# ProPrj_Flipper_-_TweenWave_2025-09-25.net
KiCad netlist of a schematic drawn in EasyEDA Pro
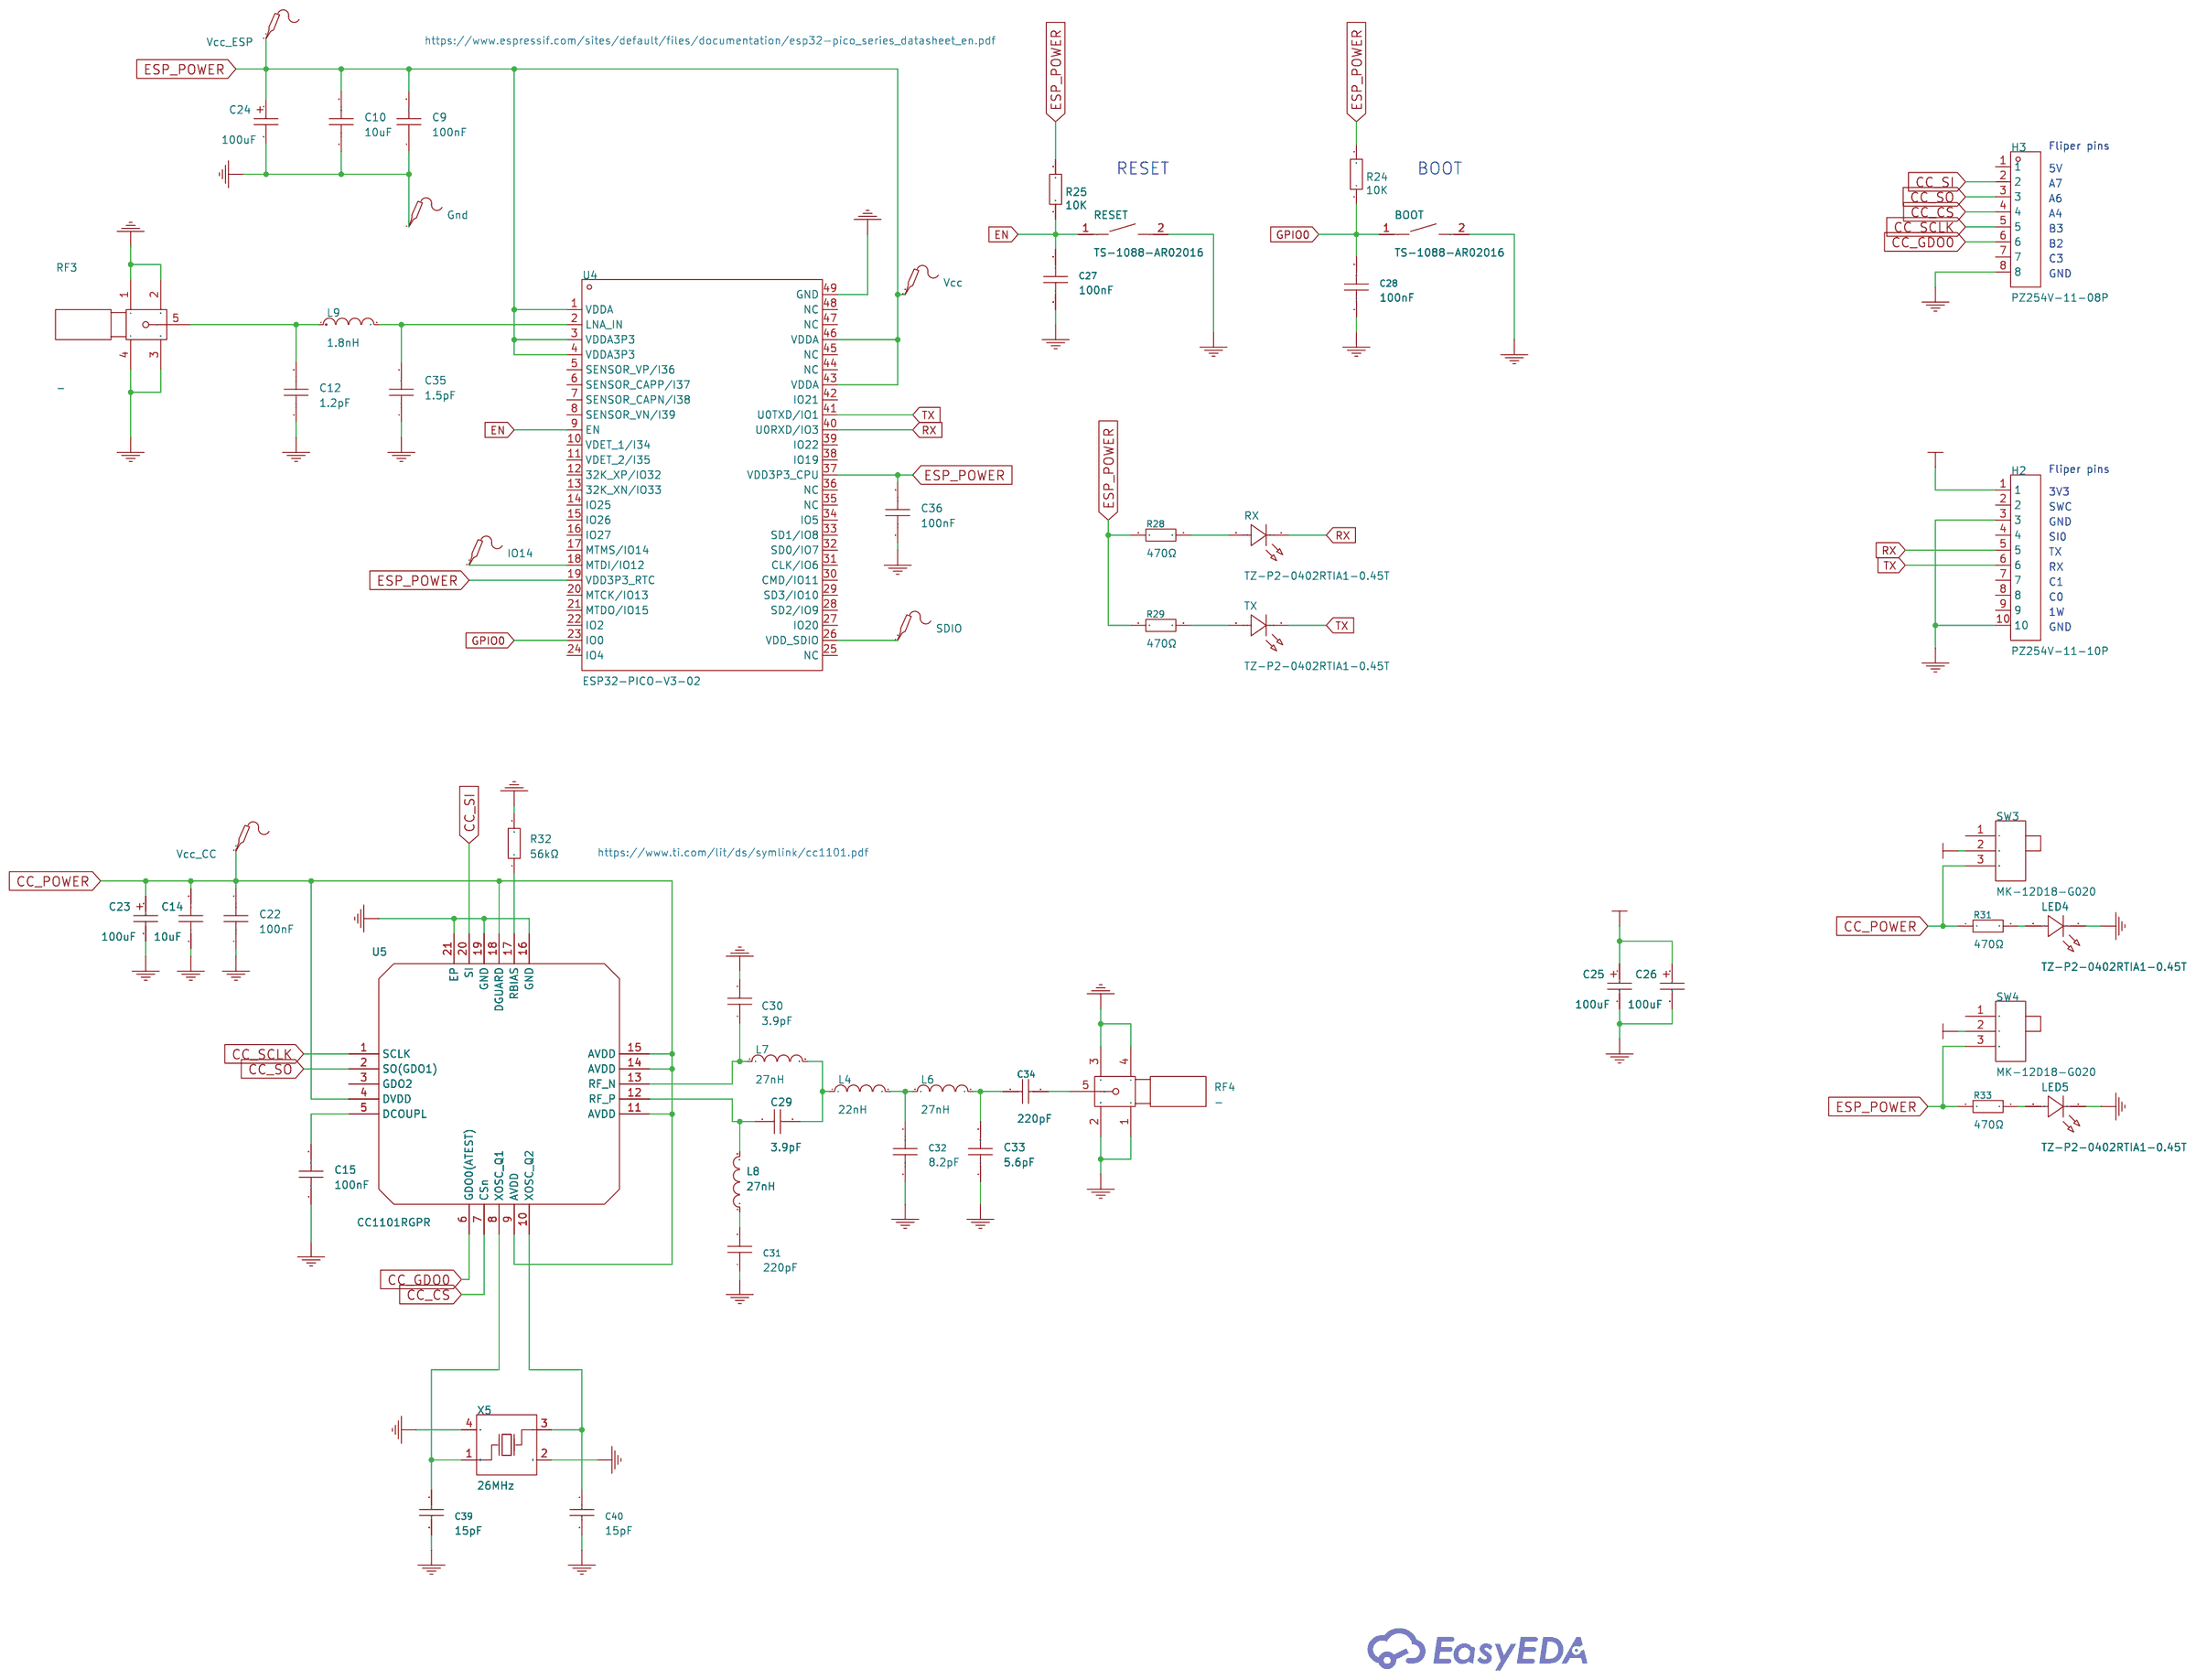
[diagram p0: schematic sheet]

(export (version "E")
  (design (tool "Eeschema 10.0.6"))
  (components
    (comp (ref "BOOT")
      (value "TS-1088-AR02016")
      (footprint "easyedapro:SW-SMD_L3.9-W3.0-P4.45")
      (fields (field (name "Manufacturer") "XUNPU(讯普)"))
      (libsource (lib "easyedapro") (part "TS-1088-AR02016"))
    )
    (comp (ref "C9")
      (value "100nF")
      (footprint "easyedapro:C0603")
      (description "Capacitance:100nF Tolerance:±10% Tolerance:±10% Voltage Rating:50V Temperature Coefficient:X7R")
      (fields
        (field (name "Manufacturer Part") "CC0603KRX7R9BB104")
        (field (name "Manufacturer") "YAGEO(国巨)")
      )
      (libsource (lib "easyedapro") (part "CC0603KRX7R9BB104"))
    )
    (comp (ref "C10")
      (value "10uF")
      (footprint "easyedapro:C0603")
      (fields
        (field (name "Manufacturer Part") "CL10A106MP8NNNC")
        (field (name "Manufacturer") "SAMSUNG(三星)")
      )
      (libsource (lib "easyedapro") (part "CL10A106MP8NNNC"))
    )
    (comp (ref "C12")
      (value "1.2pF")
      (footprint "easyedapro:C0201")
      (fields
        (field (name "Manufacturer Part") "GRM0335C1H1R2BA01D")
        (field (name "Manufacturer") "muRata(村田)")
      )
      (libsource (lib "easyedapro") (part "GRM0335C1H1R2BA01D"))
    )
    (comp (ref "C14")
      (value "10uF")
      (footprint "easyedapro:C0603")
      (fields
        (field (name "Manufacturer Part") "CL10A106MP8NNNC")
        (field (name "Manufacturer") "SAMSUNG(三星)")
      )
      (libsource (lib "easyedapro") (part "CL10A106MP8NNNC"))
    )
    (comp (ref "C15")
      (value "100nF")
      (footprint "easyedapro:C0603")
      (description "Capacitance:100nF Tolerance:±10% Tolerance:±10% Voltage Rating:50V Temperature Coefficient:X7R")
      (fields
        (field (name "Manufacturer Part") "CC0603KRX7R9BB104")
        (field (name "Manufacturer") "YAGEO(国巨)")
      )
      (libsource (lib "easyedapro") (part "CC0603KRX7R9BB104"))
    )
    (comp (ref "C22")
      (value "100nF")
      (footprint "easyedapro:C0603")
      (description "Capacitance:100nF Tolerance:±10% Tolerance:±10% Voltage Rating:50V Temperature Coefficient:X7R")
      (fields
        (field (name "Manufacturer Part") "CC0603KRX7R9BB104")
        (field (name "Manufacturer") "YAGEO(国巨)")
      )
      (libsource (lib "easyedapro") (part "CC0603KRX7R9BB104"))
    )
    (comp (ref "C23")
      (value "100uF")
      (footprint "easyedapro:CASE-B_3528")
      (fields (field (name "Manufacturer Part") "TAJB107K006RNJ") (field (name "Manufacturer") "Kyocera AVX"))
      (libsource (lib "easyedapro") (part "TAJB107K006RNJ"))
    )
    (comp (ref "C24")
      (value "100uF")
      (footprint "easyedapro:CASE-B_3528")
      (fields (field (name "Manufacturer Part") "TAJB107K006RNJ") (field (name "Manufacturer") "Kyocera AVX"))
      (libsource (lib "easyedapro") (part "TAJB107K006RNJ"))
    )
    (comp (ref "C25")
      (value "100uF")
      (footprint "easyedapro:CASE-B_3528")
      (fields (field (name "Manufacturer Part") "TAJB107K006RNJ") (field (name "Manufacturer") "Kyocera AVX"))
      (libsource (lib "easyedapro") (part "TAJB107K006RNJ"))
    )
    (comp (ref "C26")
      (value "100uF")
      (footprint "easyedapro:CASE-B_3528")
      (fields (field (name "Manufacturer Part") "TAJB107K006RNJ") (field (name "Manufacturer") "Kyocera AVX"))
      (libsource (lib "easyedapro") (part "TAJB107K006RNJ"))
    )
    (comp (ref "C27")
      (value "100nF")
      (footprint "easyedapro:C0402")
      (fields
        (field (name "Manufacturer Part") "CC0402KRX7R7BB104")
        (field (name "Manufacturer") "YAGEO(国巨)")
      )
      (libsource (lib "easyedapro") (part "CC0402KRX7R7BB104"))
    )
    (comp (ref "C28")
      (value "100nF")
      (footprint "easyedapro:C0402")
      (fields
        (field (name "Manufacturer Part") "CC0402KRX7R7BB104")
        (field (name "Manufacturer") "YAGEO(国巨)")
      )
      (libsource (lib "easyedapro") (part "CC0402KRX7R7BB104"))
    )
    (comp (ref "C29")
      (value "3.9pF")
      (footprint "easyedapro:C0402")
      (fields (field (name "Manufacturer Part") "0402CG3R9C500NT") (field (name "Manufacturer") "FH(风华)"))
      (libsource (lib "easyedapro") (part "0402CG3R9C500NT"))
    )
    (comp (ref "C30")
      (value "3.9pF")
      (footprint "easyedapro:C0402")
      (fields (field (name "Manufacturer Part") "0402CG3R9C500NT") (field (name "Manufacturer") "FH(风华)"))
      (libsource (lib "easyedapro") (part "0402CG3R9C500NT"))
    )
    (comp (ref "C31")
      (value "220pF")
      (footprint "easyedapro:C0402")
      (description "Capacitance:220pF Tolerance:±5% Tolerance:±5% Voltage Rating:50V Temperature Coefficient:NP0")
      (fields
        (field (name "Manufacturer Part") "CC0402JRNPO9BN221")
        (field (name "Manufacturer") "YAGEO(国巨)")
      )
      (libsource (lib "easyedapro") (part "CC0402JRNPO9BN221"))
    )
    (comp (ref "C32")
      (value "8.2pF")
      (footprint "easyedapro:C0402")
      (fields
        (field (name "Manufacturer Part") "CC0402BRNPO9BN8R2")
        (field (name "Manufacturer") "YAGEO(国巨)")
      )
      (libsource (lib "easyedapro") (part "CC0402BRNPO9BN8R2"))
    )
    (comp (ref "C33")
      (value "5.6pF")
      (footprint "easyedapro:C0402")
      (fields
        (field (name "Manufacturer Part") "CC0402BRNPO9BN5R6")
        (field (name "Manufacturer") "YAGEO(国巨)")
      )
      (libsource (lib "easyedapro") (part "CC0402BRNPO9BN5R6"))
    )
    (comp (ref "C34")
      (value "220pF")
      (footprint "easyedapro:C0402")
      (description "Capacitance:220pF Tolerance:±5% Tolerance:±5% Voltage Rating:50V Temperature Coefficient:NP0")
      (fields
        (field (name "Manufacturer Part") "CC0402JRNPO9BN221")
        (field (name "Manufacturer") "YAGEO(国巨)")
      )
      (libsource (lib "easyedapro") (part "CC0402JRNPO9BN221"))
    )
    (comp (ref "C35")
      (value "1.5pF")
      (footprint "easyedapro:C0201")
      (fields
        (field (name "Manufacturer Part") "GRM0335C1H1R5BA01D")
        (field (name "Manufacturer") "muRata(村田)")
      )
      (libsource (lib "easyedapro") (part "GRM0335C1H1R5BA01D"))
    )
    (comp (ref "C36")
      (value "100nF")
      (footprint "easyedapro:C0603")
      (description "Capacitance:100nF Tolerance:±10% Tolerance:±10% Voltage Rating:50V Temperature Coefficient:X7R")
      (fields
        (field (name "Manufacturer Part") "CC0603KRX7R9BB104")
        (field (name "Manufacturer") "YAGEO(国巨)")
      )
      (libsource (lib "easyedapro") (part "CC0603KRX7R9BB104"))
    )
    (comp (ref "C39")
      (value "15pF")
      (footprint "easyedapro:C0402")
      (fields
        (field (name "Manufacturer Part") "CC0402JRNPO9BN150")
        (field (name "Manufacturer") "YAGEO(国巨)")
      )
      (libsource (lib "easyedapro") (part "CC0402JRNPO9BN150"))
    )
    (comp (ref "C40")
      (value "15pF")
      (footprint "easyedapro:C0402")
      (fields
        (field (name "Manufacturer Part") "CC0402JRNPO9BN150")
        (field (name "Manufacturer") "YAGEO(国巨)")
      )
      (libsource (lib "easyedapro") (part "CC0402JRNPO9BN150"))
    )
    (comp (ref "Gnd")
      (value "~")
      (footprint "easyedapro:Test-Point-0.5mm")
      (description "Test Point 测试点")
      (libsource (lib "easyedapro") (part "Test-Point"))
    )
    (comp (ref "H2")
      (value "PZ254V-11-10P")
      (footprint "easyedapro:HDR-TH_10P-P2.54-V-M")
      (fields (field (name "Manufacturer") "XFCN(兴飞)"))
      (libsource (lib "easyedapro") (part "PZ254V-11-10P"))
    )
    (comp (ref "H3")
      (value "PZ254V-11-08P")
      (footprint "easyedapro:HDR-TH_8P-P2.54-V-M")
      (fields (field (name "Manufacturer") "XFCN(兴飞)"))
      (libsource (lib "easyedapro") (part "PZ254V-11-08P"))
    )
    (comp (ref "IO14")
      (value "~")
      (footprint "easyedapro:Test-Point-0.5mm")
      (description "Test Point 测试点")
      (libsource (lib "easyedapro") (part "Test-Point"))
    )
    (comp (ref "L4")
      (value "22nH")
      (footprint "easyedapro:L0402")
      (fields (field (name "Manufacturer Part") "LQG15HS22NJ02D") (field (name "Manufacturer") "muRata(村田)"))
      (libsource (lib "easyedapro") (part "LQG15HS22NJ02D"))
    )
    (comp (ref "L6")
      (value "27nH")
      (footprint "easyedapro:L0402-RD")
      (fields (field (name "Manufacturer Part") "LQG15HS27NJ02D") (field (name "Manufacturer") "muRata(村田)"))
      (libsource (lib "easyedapro") (part "LQG15HS27NJ02D"))
    )
    (comp (ref "L7")
      (value "27nH")
      (footprint "easyedapro:L0402-RD")
      (fields (field (name "Manufacturer Part") "LQG15HS27NJ02D") (field (name "Manufacturer") "muRata(村田)"))
      (libsource (lib "easyedapro") (part "LQG15HS27NJ02D"))
    )
    (comp (ref "L8")
      (value "27nH")
      (footprint "easyedapro:L0402-RD")
      (fields (field (name "Manufacturer Part") "LQG15HS27NJ02D") (field (name "Manufacturer") "muRata(村田)"))
      (libsource (lib "easyedapro") (part "LQG15HS27NJ02D"))
    )
    (comp (ref "L9")
      (value "1.8nH")
      (footprint "easyedapro:L0201-RD")
      (fields (field (name "Manufacturer Part") "LQP03TN1N8B02D") (field (name "Manufacturer") "muRata(村田)"))
      (libsource (lib "easyedapro") (part "LQP03TN1N8B02D"))
    )
    (comp (ref "LED4")
      (value "TZ-P2-0402RTIA1-0.45T")
      (footprint "easyedapro:LED0402-RD_RED")
      (fields (field (name "Manufacturer") "TUOZHAN(拓展光电)"))
      (libsource (lib "easyedapro") (part "TZ-P2-0402RTIA1-0.45T"))
    )
    (comp (ref "LED5")
      (value "TZ-P2-0402RTIA1-0.45T")
      (footprint "easyedapro:LED0402-RD_RED")
      (fields (field (name "Manufacturer") "TUOZHAN(拓展光电)"))
      (libsource (lib "easyedapro") (part "TZ-P2-0402RTIA1-0.45T"))
    )
    (comp (ref "R24")
      (value "10K")
      (footprint "easyedapro:R0603")
      (fields (field (name "Manufacturer Part") "RC0603DR-0710KL") (field (name "Manufacturer") "YAGEO(国巨)"))
      (libsource (lib "easyedapro") (part "10K"))
    )
    (comp (ref "R25")
      (value "10K")
      (footprint "easyedapro:R0603")
      (fields (field (name "Manufacturer Part") "RC0603DR-0710KL") (field (name "Manufacturer") "YAGEO(国巨)"))
      (libsource (lib "easyedapro") (part "10K"))
    )
    (comp (ref "R28")
      (value "470Ω")
      (footprint "easyedapro:R0402")
      (fields
        (field (name "Manufacturer Part") "0402WGF4700TCE")
        (field (name "Manufacturer") "UNI-ROYAL(厚声)")
      )
      (libsource (lib "easyedapro") (part "0402WGF4700TCE"))
    )
    (comp (ref "R29")
      (value "470Ω")
      (footprint "easyedapro:R0402")
      (fields
        (field (name "Manufacturer Part") "0402WGF4700TCE")
        (field (name "Manufacturer") "UNI-ROYAL(厚声)")
      )
      (libsource (lib "easyedapro") (part "0402WGF4700TCE"))
    )
    (comp (ref "R31")
      (value "470Ω")
      (footprint "easyedapro:R0402")
      (fields
        (field (name "Manufacturer Part") "0402WGF4700TCE")
        (field (name "Manufacturer") "UNI-ROYAL(厚声)")
      )
      (libsource (lib "easyedapro") (part "0402WGF4700TCE"))
    )
    (comp (ref "R32")
      (value "56kΩ")
      (footprint "easyedapro:R0402")
      (fields
        (field (name "Manufacturer Part") "0402WGF5602TCE")
        (field (name "Manufacturer") "UNI-ROYAL(厚声)")
      )
      (libsource (lib "easyedapro") (part "0402WGF5602TCE"))
    )
    (comp (ref "R33")
      (value "470Ω")
      (footprint "easyedapro:R0402")
      (fields
        (field (name "Manufacturer Part") "0402WGF4700TCE")
        (field (name "Manufacturer") "UNI-ROYAL(厚声)")
      )
      (libsource (lib "easyedapro") (part "0402WGF4700TCE"))
    )
    (comp (ref "RESET")
      (value "TS-1088-AR02016")
      (footprint "easyedapro:SW-SMD_L3.9-W3.0-P4.45")
      (fields (field (name "Manufacturer") "XUNPU(讯普)"))
      (libsource (lib "easyedapro") (part "TS-1088-AR02016"))
    )
    (comp (ref "RF3")
      (value "-")
      (footprint "easyedapro:SMA-SMD_BWSMA-KE-P001")
      (fields
        (field (name "Manufacturer Part") "BWSMA-KE-P001")
        (field (name "Manufacturer") "BAT WIRELESS(蝙蝠无线)")
      )
      (libsource (lib "easyedapro") (part "BWSMA-KE-P001"))
    )
    (comp (ref "RF4")
      (value "-")
      (footprint "easyedapro:SMA-SMD_BWSMA-KE-P001")
      (fields
        (field (name "Manufacturer Part") "BWSMA-KE-P001")
        (field (name "Manufacturer") "BAT WIRELESS(蝙蝠无线)")
      )
      (libsource (lib "easyedapro") (part "BWSMA-KE-P001"))
    )
    (comp (ref "RX")
      (value "TZ-P2-0402RTIA1-0.45T")
      (footprint "easyedapro:LED0402-RD_RED")
      (fields (field (name "Manufacturer") "TUOZHAN(拓展光电)"))
      (libsource (lib "easyedapro") (part "TZ-P2-0402RTIA1-0.45T"))
    )
    (comp (ref "SDIO")
      (value "~")
      (footprint "easyedapro:Test-Point-0.5mm")
      (description "Test Point 测试点")
      (libsource (lib "easyedapro") (part "Test-Point"))
    )
    (comp (ref "SW3")
      (value "MK-12D18-G020")
      (footprint "easyedapro:SW-TH_MK-12D18-G040")
      (fields (field (name "Manufacturer") "G-Switch(品赞)"))
      (libsource (lib "easyedapro") (part "MK-12D18-G020"))
    )
    (comp (ref "SW4")
      (value "MK-12D18-G020")
      (footprint "easyedapro:SW-TH_MK-12D18-G040")
      (fields (field (name "Manufacturer") "G-Switch(品赞)"))
      (libsource (lib "easyedapro") (part "MK-12D18-G020"))
    )
    (comp (ref "TX")
      (value "TZ-P2-0402RTIA1-0.45T")
      (footprint "easyedapro:LED0402-RD_RED")
      (fields (field (name "Manufacturer") "TUOZHAN(拓展光电)"))
      (libsource (lib "easyedapro") (part "TZ-P2-0402RTIA1-0.45T"))
    )
    (comp (ref "U4")
      (value "ESP32-PICO-V3-02")
      (footprint "easyedapro:QFN-48_L7.0-W7.0-P0.50-BL-EP5.1")
      (fields (field (name "Manufacturer") "ESPRESSIF(乐鑫)"))
      (libsource (lib "easyedapro") (part "ESP32-PICO-V3-02"))
    )
    (comp (ref "U5")
      (value "CC1101RGPR")
      (footprint "easyedapro:QFN-20_L4.0-W4.0-P0.5-TL-EP")
      (fields (field (name "Manufacturer") "TI(德州仪器)"))
      (libsource (lib "easyedapro") (part "CC1101RGPR"))
    )
    (comp (ref "Vcc")
      (value "~")
      (footprint "easyedapro:Test-Point-0.5mm")
      (description "Test Point 测试点")
      (libsource (lib "easyedapro") (part "Test-Point"))
    )
    (comp (ref "Vcc_CC")
      (value "~")
      (footprint "easyedapro:Test-Point-0.5mm")
      (description "Test Point 测试点")
      (libsource (lib "easyedapro") (part "Test-Point"))
    )
    (comp (ref "Vcc_ESP")
      (value "~")
      (footprint "easyedapro:Test-Point-0.5mm")
      (description "Test Point 测试点")
      (libsource (lib "easyedapro") (part "Test-Point"))
    )
    (comp (ref "X5")
      (value "26MHz")
      (footprint "easyedapro:CRYSTAL-SMD_4P-L3.2-W2.5-BL")
      (fields (field (name "Manufacturer Part") "X322526MMB4SI") (field (name "Manufacturer") "YXC(扬兴晶振)"))
      (libsource (lib "easyedapro") (part "X322526MMB4SI"))
    )
  )
  (nets
    (net (code "1") (name "3V3") (class "Default")
      (node (ref "C25") (pin "1") (pinfunction "1_1") (pintype "input"))
      (node (ref "C26") (pin "1") (pinfunction "1_1") (pintype "input"))
      (node (ref "H2") (pin "1") (pinfunction "1_1") (pintype "unspecified"))
      (node (ref "SW3") (pin "2") (pinfunction "2_2") (pintype "unspecified"))
      (node (ref "SW4") (pin "2") (pinfunction "2_2") (pintype "unspecified"))
    )
    (net (code "2") (name "CC_CS") (class "Default")
      (node (ref "H3") (pin "4") (pinfunction "4_4") (pintype "unspecified"))
      (node (ref "U5") (pin "7") (pinfunction "CSn_7") (pintype "unspecified"))
    )
    (net (code "3") (name "CC_GDO0") (class "Default")
      (node (ref "H3") (pin "6") (pinfunction "6_6") (pintype "unspecified"))
      (node (ref "U5") (pin "6") (pinfunction "GDO0(ATEST)_6") (pintype "unspecified"))
    )
    (net (code "4") (name "CC_POWER") (class "Default")
      (node (ref "C14") (pin "2") (pinfunction "2_2") (pintype "unspecified"))
      (node (ref "C22") (pin "2") (pinfunction "2_2") (pintype "unspecified"))
      (node (ref "C23") (pin "1") (pinfunction "1_1") (pintype "input"))
      (node (ref "R31") (pin "1") (pinfunction "1_1") (pintype "input"))
      (node (ref "SW3") (pin "3") (pinfunction "3_3") (pintype "unspecified"))
      (node (ref "U5") (pin "11") (pinfunction "AVDD_11") (pintype "unspecified"))
      (node (ref "U5") (pin "14") (pinfunction "AVDD_14") (pintype "unspecified"))
      (node (ref "U5") (pin "15") (pinfunction "AVDD_15") (pintype "unspecified"))
      (node (ref "U5") (pin "18") (pinfunction "DGUARD_18") (pintype "unspecified"))
      (node (ref "U5") (pin "4") (pinfunction "DVDD_4") (pintype "unspecified"))
      (node (ref "U5") (pin "9") (pinfunction "AVDD_9") (pintype "unspecified"))
      (node (ref "Vcc_CC") (pin "1") (pinfunction "1_1") (pintype "unspecified"))
    )
    (net (code "5") (name "CC_SCLK") (class "Default")
      (node (ref "H3") (pin "5") (pinfunction "5_5") (pintype "unspecified"))
      (node (ref "U5") (pin "1") (pinfunction "SCLK_1") (pintype "unspecified"))
    )
    (net (code "6") (name "CC_SI") (class "Default")
      (node (ref "H3") (pin "2") (pinfunction "2_2") (pintype "unspecified"))
      (node (ref "U5") (pin "20") (pinfunction "SI_20") (pintype "unspecified"))
    )
    (net (code "7") (name "CC_SO") (class "Default")
      (node (ref "H3") (pin "3") (pinfunction "3_3") (pintype "unspecified"))
      (node (ref "U5") (pin "2") (pinfunction "SO(GDO1)_2") (pintype "unspecified"))
    )
    (net (code "8") (name "EN") (class "Default")
      (node (ref "C27") (pin "2") (pinfunction "2_2") (pintype "input"))
      (node (ref "R25") (pin "1") (pinfunction "1_1") (pintype "input"))
      (node (ref "RESET") (pin "1") (pinfunction "1_1") (pintype "unspecified"))
      (node (ref "U4") (pin "9") (pinfunction "EN_9") (pintype "unspecified"))
    )
    (net (code "9") (name "ESP_POWER") (class "Default")
      (node (ref "C10") (pin "2") (pinfunction "2_2") (pintype "unspecified"))
      (node (ref "C24") (pin "1") (pinfunction "1_1") (pintype "input"))
      (node (ref "C36") (pin "2") (pinfunction "2_2") (pintype "unspecified"))
      (node (ref "C9") (pin "2") (pinfunction "2_2") (pintype "unspecified"))
      (node (ref "R24") (pin "2") (pinfunction "2_2") (pintype "input"))
      (node (ref "R25") (pin "2") (pinfunction "2_2") (pintype "input"))
      (node (ref "R28") (pin "1") (pinfunction "1_1") (pintype "input"))
      (node (ref "R29") (pin "1") (pinfunction "1_1") (pintype "input"))
      (node (ref "R33") (pin "1") (pinfunction "1_1") (pintype "input"))
      (node (ref "SW4") (pin "3") (pinfunction "3_3") (pintype "unspecified"))
      (node (ref "U4") (pin "1") (pinfunction "VDDA_1") (pintype "unspecified"))
      (node (ref "U4") (pin "19") (pinfunction "VDD3P3_RTC_19") (pintype "unspecified"))
      (node (ref "U4") (pin "3") (pinfunction "VDDA3P3_3") (pintype "unspecified"))
      (node (ref "U4") (pin "37") (pinfunction "VDD3P3_CPU_37") (pintype "unspecified"))
      (node (ref "U4") (pin "4") (pinfunction "VDDA3P3_4") (pintype "unspecified"))
      (node (ref "U4") (pin "43") (pinfunction "VDDA_43") (pintype "unspecified"))
      (node (ref "U4") (pin "46") (pinfunction "VDDA_46") (pintype "unspecified"))
      (node (ref "Vcc") (pin "1") (pinfunction "1_1") (pintype "unspecified"))
      (node (ref "Vcc_ESP") (pin "1") (pinfunction "1_1") (pintype "unspecified"))
    )
    (net (code "10") (name "GND") (class "Default")
      (node (ref "BOOT") (pin "2") (pinfunction "2_2") (pintype "unspecified"))
      (node (ref "C10") (pin "1") (pinfunction "1_1") (pintype "unspecified"))
      (node (ref "C12") (pin "1") (pinfunction "1_1") (pintype "unspecified"))
      (node (ref "C14") (pin "1") (pinfunction "1_1") (pintype "unspecified"))
      (node (ref "C15") (pin "1") (pinfunction "1_1") (pintype "unspecified"))
      (node (ref "C22") (pin "1") (pinfunction "1_1") (pintype "unspecified"))
      (node (ref "C23") (pin "2") (pinfunction "2_2") (pintype "input"))
      (node (ref "C24") (pin "2") (pinfunction "2_2") (pintype "input"))
      (node (ref "C25") (pin "2") (pinfunction "2_2") (pintype "input"))
      (node (ref "C26") (pin "2") (pinfunction "2_2") (pintype "input"))
      (node (ref "C27") (pin "1") (pinfunction "1_1") (pintype "input"))
      (node (ref "C28") (pin "1") (pinfunction "1_1") (pintype "input"))
      (node (ref "C30") (pin "2") (pinfunction "2_2") (pintype "input"))
      (node (ref "C31") (pin "1") (pinfunction "1_1") (pintype "input"))
      (node (ref "C32") (pin "2") (pinfunction "2_2") (pintype "input"))
      (node (ref "C33") (pin "1") (pinfunction "1_1") (pintype "unspecified"))
      (node (ref "C35") (pin "1") (pinfunction "1_1") (pintype "unspecified"))
      (node (ref "C36") (pin "1") (pinfunction "1_1") (pintype "unspecified"))
      (node (ref "C39") (pin "1") (pinfunction "1_1") (pintype "input"))
      (node (ref "C40") (pin "1") (pinfunction "1_1") (pintype "input"))
      (node (ref "C9") (pin "1") (pinfunction "1_1") (pintype "unspecified"))
      (node (ref "Gnd") (pin "1") (pinfunction "1_1") (pintype "unspecified"))
      (node (ref "H2") (pin "10") (pinfunction "10_10") (pintype "unspecified"))
      (node (ref "H2") (pin "3") (pinfunction "3_3") (pintype "unspecified"))
      (node (ref "H3") (pin "8") (pinfunction "8_8") (pintype "unspecified"))
      (node (ref "LED4") (pin "1") (pinfunction "K_1") (pintype "unspecified"))
      (node (ref "LED5") (pin "1") (pinfunction "K_1") (pintype "unspecified"))
      (node (ref "R32") (pin "2") (pinfunction "2_2") (pintype "input"))
      (node (ref "RESET") (pin "2") (pinfunction "2_2") (pintype "unspecified"))
      (node (ref "RF3") (pin "1") (pinfunction "1_1") (pintype "unspecified"))
      (node (ref "RF3") (pin "2") (pinfunction "2_2") (pintype "unspecified"))
      (node (ref "RF3") (pin "3") (pinfunction "3_3") (pintype "unspecified"))
      (node (ref "RF3") (pin "4") (pinfunction "4_4") (pintype "unspecified"))
      (node (ref "RF4") (pin "1") (pinfunction "1_1") (pintype "unspecified"))
      (node (ref "RF4") (pin "2") (pinfunction "2_2") (pintype "unspecified"))
      (node (ref "RF4") (pin "3") (pinfunction "3_3") (pintype "unspecified"))
      (node (ref "RF4") (pin "4") (pinfunction "4_4") (pintype "unspecified"))
      (node (ref "U4") (pin "49") (pinfunction "GND_49") (pintype "unspecified"))
      (node (ref "U5") (pin "16") (pinfunction "GND_16") (pintype "unspecified"))
      (node (ref "U5") (pin "19") (pinfunction "GND_19") (pintype "unspecified"))
      (node (ref "U5") (pin "21") (pinfunction "EP_21") (pintype "unspecified"))
      (node (ref "X5") (pin "2") (pinfunction "GND_2") (pintype "unspecified"))
      (node (ref "X5") (pin "4") (pinfunction "GND_4") (pintype "unspecified"))
    )
    (net (code "11") (name "GPIO0") (class "Default")
      (node (ref "BOOT") (pin "1") (pinfunction "1_1") (pintype "unspecified"))
      (node (ref "C28") (pin "2") (pinfunction "2_2") (pintype "input"))
      (node (ref "R24") (pin "1") (pinfunction "1_1") (pintype "input"))
      (node (ref "U4") (pin "23") (pinfunction "IO0_23") (pintype "unspecified"))
    )
    (net (code "12") (name "Net-(C12-Pad2)") (class "Default")
      (node (ref "C12") (pin "2") (pinfunction "2_2") (pintype "unspecified"))
      (node (ref "L9") (pin "1") (pinfunction "1_1") (pintype "input"))
      (node (ref "RF3") (pin "5") (pinfunction "5_5") (pintype "unspecified"))
    )
    (net (code "13") (name "Net-(C29-Pad2)") (class "Default")
      (node (ref "C29") (pin "2") (pinfunction "2_2") (pintype "input"))
      (node (ref "L4") (pin "1") (pinfunction "1_1") (pintype "unspecified"))
      (node (ref "L7") (pin "2") (pinfunction "2_2") (pintype "unspecified"))
    )
    (net (code "14") (name "Net-(C31-Pad2)") (class "Default")
      (node (ref "C31") (pin "2") (pinfunction "2_2") (pintype "input"))
      (node (ref "L8") (pin "1") (pinfunction "1_1") (pintype "unspecified"))
    )
    (net (code "15") (name "Net-(C32-Pad1)") (class "Default")
      (node (ref "C32") (pin "1") (pinfunction "1_1") (pintype "input"))
      (node (ref "L4") (pin "2") (pinfunction "2_2") (pintype "unspecified"))
      (node (ref "L6") (pin "1") (pinfunction "1_1") (pintype "unspecified"))
    )
    (net (code "16") (name "Net-(C33-Pad2)") (class "Default")
      (node (ref "C33") (pin "2") (pinfunction "2_2") (pintype "unspecified"))
      (node (ref "C34") (pin "2") (pinfunction "2_2") (pintype "input"))
      (node (ref "L6") (pin "2") (pinfunction "2_2") (pintype "unspecified"))
    )
    (net (code "17") (name "Net-(C34-Pad1)") (class "Default")
      (node (ref "C34") (pin "1") (pinfunction "1_1") (pintype "input"))
      (node (ref "RF4") (pin "5") (pinfunction "5_5") (pintype "unspecified"))
    )
    (net (code "18") (name "Net-(LED4-A)") (class "Default")
      (node (ref "LED4") (pin "2") (pinfunction "A_2") (pintype "unspecified"))
      (node (ref "R31") (pin "2") (pinfunction "2_2") (pintype "input"))
    )
    (net (code "19") (name "Net-(LED5-A)") (class "Default")
      (node (ref "LED5") (pin "2") (pinfunction "A_2") (pintype "unspecified"))
      (node (ref "R33") (pin "2") (pinfunction "2_2") (pintype "input"))
    )
    (net (code "20") (name "Net-(RX-A)") (class "Default")
      (node (ref "R28") (pin "2") (pinfunction "2_2") (pintype "input"))
      (node (ref "RX") (pin "2") (pinfunction "A_2") (pintype "unspecified"))
    )
    (net (code "21") (name "Net-(TX-A)") (class "Default")
      (node (ref "R29") (pin "2") (pinfunction "2_2") (pintype "input"))
      (node (ref "TX") (pin "2") (pinfunction "A_2") (pintype "unspecified"))
    )
    (net (code "22") (name "Net-(U4-LNA_IN)") (class "Default")
      (node (ref "C35") (pin "2") (pinfunction "2_2") (pintype "unspecified"))
      (node (ref "L9") (pin "2") (pinfunction "2_2") (pintype "input"))
      (node (ref "U4") (pin "2") (pinfunction "LNA_IN_2") (pintype "unspecified"))
    )
    (net (code "23") (name "Net-(U4-MTDI{slash}IO12)") (class "Default")
      (node (ref "IO14") (pin "1") (pinfunction "1_1") (pintype "unspecified"))
      (node (ref "U4") (pin "18") (pinfunction "MTDI/IO12_18") (pintype "unspecified"))
    )
    (net (code "24") (name "Net-(U4-VDD_SDIO)") (class "Default")
      (node (ref "SDIO") (pin "1") (pinfunction "1_1") (pintype "unspecified"))
      (node (ref "U4") (pin "26") (pinfunction "VDD_SDIO_26") (pintype "unspecified"))
    )
    (net (code "25") (name "Net-(U5-DCOUPL)") (class "Default")
      (node (ref "C15") (pin "2") (pinfunction "2_2") (pintype "unspecified"))
      (node (ref "U5") (pin "5") (pinfunction "DCOUPL_5") (pintype "unspecified"))
    )
    (net (code "26") (name "Net-(U5-RBIAS)") (class "Default")
      (node (ref "R32") (pin "1") (pinfunction "1_1") (pintype "input"))
      (node (ref "U5") (pin "17") (pinfunction "RBIAS_17") (pintype "unspecified"))
    )
    (net (code "27") (name "Net-(U5-RF_N)") (class "Default")
      (node (ref "C30") (pin "1") (pinfunction "1_1") (pintype "input"))
      (node (ref "L7") (pin "1") (pinfunction "1_1") (pintype "unspecified"))
      (node (ref "U5") (pin "13") (pinfunction "RF_N_13") (pintype "unspecified"))
    )
    (net (code "28") (name "Net-(U5-RF_P)") (class "Default")
      (node (ref "C29") (pin "1") (pinfunction "1_1") (pintype "input"))
      (node (ref "L8") (pin "2") (pinfunction "2_2") (pintype "unspecified"))
      (node (ref "U5") (pin "12") (pinfunction "RF_P_12") (pintype "unspecified"))
    )
    (net (code "29") (name "Net-(U5-XOSC_Q1)") (class "Default")
      (node (ref "C39") (pin "2") (pinfunction "2_2") (pintype "input"))
      (node (ref "U5") (pin "8") (pinfunction "XOSC_Q1_8") (pintype "unspecified"))
      (node (ref "X5") (pin "1") (pinfunction "OSC1_1") (pintype "unspecified"))
    )
    (net (code "30") (name "Net-(U5-XOSC_Q2)") (class "Default")
      (node (ref "C40") (pin "2") (pinfunction "2_2") (pintype "input"))
      (node (ref "U5") (pin "10") (pinfunction "XOSC_Q2_10") (pintype "unspecified"))
      (node (ref "X5") (pin "3") (pinfunction "OSC2_3") (pintype "unspecified"))
    )
    (net (code "31") (name "RX") (class "Default")
      (node (ref "H2") (pin "5") (pinfunction "5_5") (pintype "unspecified"))
      (node (ref "RX") (pin "1") (pinfunction "K_1") (pintype "unspecified"))
      (node (ref "U4") (pin "40") (pinfunction "U0RXD/IO3_40") (pintype "unspecified"))
    )
    (net (code "32") (name "TX") (class "Default")
      (node (ref "H2") (pin "6") (pinfunction "6_6") (pintype "unspecified"))
      (node (ref "TX") (pin "1") (pinfunction "K_1") (pintype "unspecified"))
      (node (ref "U4") (pin "41") (pinfunction "U0TXD/IO1_41") (pintype "unspecified"))
    )
    (net (code "33") (name "unconnected-(H2-Pad2)") (class "Default")
      (node (ref "H2") (pin "2") (pinfunction "2_2") (pintype "unspecified"))
    )
    (net (code "34") (name "unconnected-(H2-Pad4)") (class "Default")
      (node (ref "H2") (pin "4") (pinfunction "4_4") (pintype "unspecified"))
    )
    (net (code "35") (name "unconnected-(H2-Pad7)") (class "Default")
      (node (ref "H2") (pin "7") (pinfunction "7_7") (pintype "unspecified"))
    )
    (net (code "36") (name "unconnected-(H2-Pad8)") (class "Default")
      (node (ref "H2") (pin "8") (pinfunction "8_8") (pintype "unspecified"))
    )
    (net (code "37") (name "unconnected-(H2-Pad9)") (class "Default")
      (node (ref "H2") (pin "9") (pinfunction "9_9") (pintype "unspecified"))
    )
    (net (code "38") (name "unconnected-(H3-Pad1)") (class "Default")
      (node (ref "H3") (pin "1") (pinfunction "1_1") (pintype "unspecified"))
    )
    (net (code "39") (name "unconnected-(H3-Pad7)") (class "Default")
      (node (ref "H3") (pin "7") (pinfunction "7_7") (pintype "unspecified"))
    )
    (net (code "40") (name "unconnected-(SW3-Pad1)") (class "Default")
      (node (ref "SW3") (pin "1") (pinfunction "1_1") (pintype "unspecified"))
    )
    (net (code "41") (name "unconnected-(SW4-Pad1)") (class "Default")
      (node (ref "SW4") (pin "1") (pinfunction "1_1") (pintype "unspecified"))
    )
    (net (code "42") (name "unconnected-(U4-32K_XN{slash}IO33-Pad13)") (class "Default")
      (node (ref "U4") (pin "13") (pinfunction "32K_XN/IO33_13") (pintype "unspecified"))
    )
    (net (code "43") (name "unconnected-(U4-32K_XP{slash}IO32-Pad12)") (class "Default")
      (node (ref "U4") (pin "12") (pinfunction "32K_XP/IO32_12") (pintype "unspecified"))
    )
    (net (code "44") (name "unconnected-(U4-CLK{slash}IO6-Pad31)") (class "Default")
      (node (ref "U4") (pin "31") (pinfunction "CLK/IO6_31") (pintype "unspecified"))
    )
    (net (code "45") (name "unconnected-(U4-CMD{slash}IO11-Pad30)") (class "Default")
      (node (ref "U4") (pin "30") (pinfunction "CMD/IO11_30") (pintype "unspecified"))
    )
    (net (code "46") (name "unconnected-(U4-IO2-Pad22)") (class "Default")
      (node (ref "U4") (pin "22") (pinfunction "IO2_22") (pintype "unspecified"))
    )
    (net (code "47") (name "unconnected-(U4-IO4-Pad24)") (class "Default")
      (node (ref "U4") (pin "24") (pinfunction "IO4_24") (pintype "unspecified"))
    )
    (net (code "48") (name "unconnected-(U4-IO5-Pad34)") (class "Default")
      (node (ref "U4") (pin "34") (pinfunction "IO5_34") (pintype "unspecified"))
    )
    (net (code "49") (name "unconnected-(U4-IO19-Pad38)") (class "Default")
      (node (ref "U4") (pin "38") (pinfunction "IO19_38") (pintype "unspecified"))
    )
    (net (code "50") (name "unconnected-(U4-IO20-Pad27)") (class "Default")
      (node (ref "U4") (pin "27") (pinfunction "IO20_27") (pintype "unspecified"))
    )
    (net (code "51") (name "unconnected-(U4-IO21-Pad42)") (class "Default")
      (node (ref "U4") (pin "42") (pinfunction "IO21_42") (pintype "unspecified"))
    )
    (net (code "52") (name "unconnected-(U4-IO22-Pad39)") (class "Default")
      (node (ref "U4") (pin "39") (pinfunction "IO22_39") (pintype "unspecified"))
    )
    (net (code "53") (name "unconnected-(U4-IO25-Pad14)") (class "Default")
      (node (ref "U4") (pin "14") (pinfunction "IO25_14") (pintype "unspecified"))
    )
    (net (code "54") (name "unconnected-(U4-IO26-Pad15)") (class "Default")
      (node (ref "U4") (pin "15") (pinfunction "IO26_15") (pintype "unspecified"))
    )
    (net (code "55") (name "unconnected-(U4-IO27-Pad16)") (class "Default")
      (node (ref "U4") (pin "16") (pinfunction "IO27_16") (pintype "unspecified"))
    )
    (net (code "56") (name "unconnected-(U4-MTCK{slash}IO13-Pad20)") (class "Default")
      (node (ref "U4") (pin "20") (pinfunction "MTCK/IO13_20") (pintype "unspecified"))
    )
    (net (code "57") (name "unconnected-(U4-MTDO{slash}IO15-Pad21)") (class "Default")
      (node (ref "U4") (pin "21") (pinfunction "MTDO/IO15_21") (pintype "unspecified"))
    )
    (net (code "58") (name "unconnected-(U4-MTMS{slash}IO14-Pad17)") (class "Default")
      (node (ref "U4") (pin "17") (pinfunction "MTMS/IO14_17") (pintype "unspecified"))
    )
    (net (code "59") (name "unconnected-(U4-NC-Pad25)") (class "Default")
      (node (ref "U4") (pin "25") (pinfunction "NC_25") (pintype "unspecified"))
    )
    (net (code "60") (name "unconnected-(U4-NC-Pad35)") (class "Default")
      (node (ref "U4") (pin "35") (pinfunction "NC_35") (pintype "unspecified"))
    )
    (net (code "61") (name "unconnected-(U4-NC-Pad36)") (class "Default")
      (node (ref "U4") (pin "36") (pinfunction "NC_36") (pintype "unspecified"))
    )
    (net (code "62") (name "unconnected-(U4-NC-Pad44)") (class "Default")
      (node (ref "U4") (pin "44") (pinfunction "NC_44") (pintype "unspecified"))
    )
    (net (code "63") (name "unconnected-(U4-NC-Pad45)") (class "Default")
      (node (ref "U4") (pin "45") (pinfunction "NC_45") (pintype "unspecified"))
    )
    (net (code "64") (name "unconnected-(U4-NC-Pad47)") (class "Default")
      (node (ref "U4") (pin "47") (pinfunction "NC_47") (pintype "unspecified"))
    )
    (net (code "65") (name "unconnected-(U4-NC-Pad48)") (class "Default")
      (node (ref "U4") (pin "48") (pinfunction "NC_48") (pintype "unspecified"))
    )
    (net (code "66") (name "unconnected-(U4-SD0{slash}IO7-Pad32)") (class "Default")
      (node (ref "U4") (pin "32") (pinfunction "SD0/IO7_32") (pintype "unspecified"))
    )
    (net (code "67") (name "unconnected-(U4-SD1{slash}IO8-Pad33)") (class "Default")
      (node (ref "U4") (pin "33") (pinfunction "SD1/IO8_33") (pintype "unspecified"))
    )
    (net (code "68") (name "unconnected-(U4-SD2{slash}IO9-Pad28)") (class "Default")
      (node (ref "U4") (pin "28") (pinfunction "SD2/IO9_28") (pintype "unspecified"))
    )
    (net (code "69") (name "unconnected-(U4-SD3{slash}IO10-Pad29)") (class "Default")
      (node (ref "U4") (pin "29") (pinfunction "SD3/IO10_29") (pintype "unspecified"))
    )
    (net (code "70") (name "unconnected-(U4-SENSOR_CAPN{slash}I38-Pad7)") (class "Default")
      (node (ref "U4") (pin "7") (pinfunction "SENSOR_CAPN/I38_7") (pintype "unspecified"))
    )
    (net (code "71") (name "unconnected-(U4-SENSOR_CAPP{slash}I37-Pad6)") (class "Default")
      (node (ref "U4") (pin "6") (pinfunction "SENSOR_CAPP/I37_6") (pintype "unspecified"))
    )
    (net (code "72") (name "unconnected-(U4-SENSOR_VN{slash}I39-Pad8)") (class "Default")
      (node (ref "U4") (pin "8") (pinfunction "SENSOR_VN/I39_8") (pintype "unspecified"))
    )
    (net (code "73") (name "unconnected-(U4-SENSOR_VP{slash}I36-Pad5)") (class "Default")
      (node (ref "U4") (pin "5") (pinfunction "SENSOR_VP/I36_5") (pintype "unspecified"))
    )
    (net (code "74") (name "unconnected-(U4-VDET_1{slash}I34-Pad10)") (class "Default")
      (node (ref "U4") (pin "10") (pinfunction "VDET_1/I34_10") (pintype "unspecified"))
    )
    (net (code "75") (name "unconnected-(U4-VDET_2{slash}I35-Pad11)") (class "Default")
      (node (ref "U4") (pin "11") (pinfunction "VDET_2/I35_11") (pintype "unspecified"))
    )
    (net (code "76") (name "unconnected-(U5-GDO2-Pad3)") (class "Default")
      (node (ref "U5") (pin "3") (pinfunction "GDO2_3") (pintype "unspecified"))
    )
  )
)
